# low_pass.net
KiCad netlist of a schematic drawn in Altium Designer
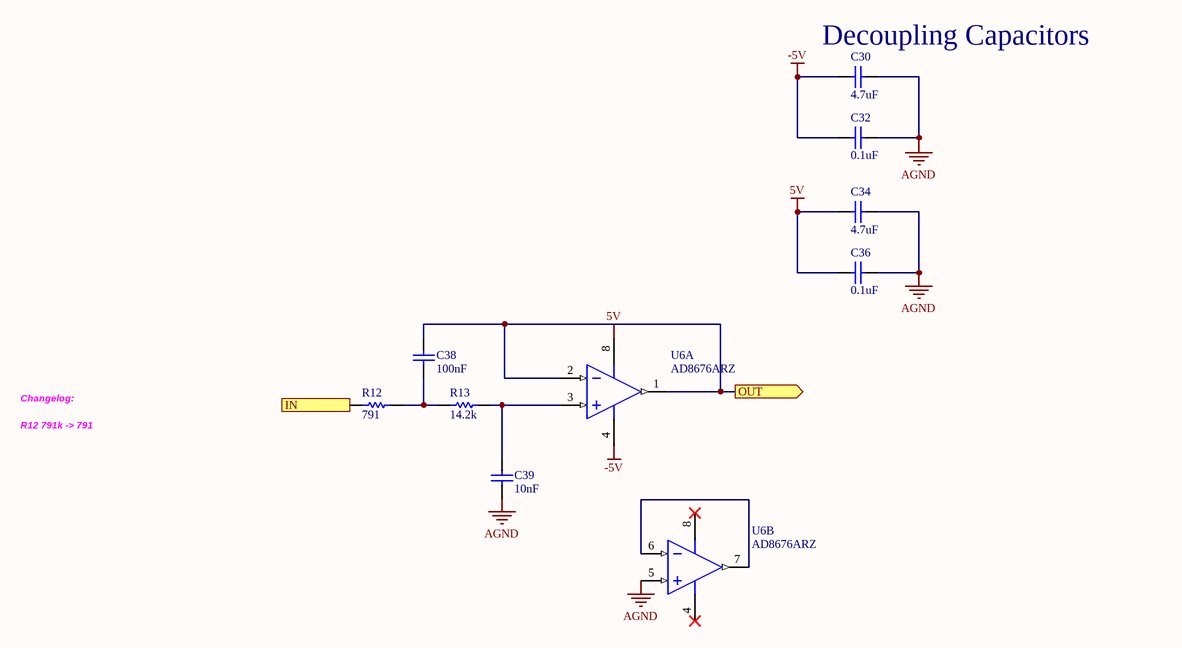
[diagram p0: low_pass.SchDoc]

(export (version "E")
  (design (tool "Eeschema 10.0.6"))
  (components
    (comp (ref "C30")
      (value "4.7uF")
      (footprint "0402_Cap")
      (description "Capacitor, 4.7uF, 0805")
      (libsource (lib "Arturo_Approved") (part "CL21A475KAQNNNE"))
    )
    (comp (ref "C32")
      (value "0.1uF")
      (footprint "0402_Cap")
      (description "Capacitor, 0.1uF, 0805")
      (libsource (lib "Arturo_Approved") (part "CL21B104KACNNNC"))
    )
    (comp (ref "C34")
      (value "4.7uF")
      (footprint "0402_Cap")
      (description "Capacitor, 4.7uF, 0805")
      (libsource (lib "Arturo_Approved") (part "CL21A475KAQNNNE"))
    )
    (comp (ref "C36")
      (value "0.1uF")
      (footprint "0402_Cap")
      (description "Capacitor, 0.1uF, 0805")
      (libsource (lib "Arturo_Approved") (part "CL21B104KACNNNC"))
    )
    (comp (ref "C38")
      (value "100nF")
      (footprint "0402_Cap")
      (description "Capacitor, 16nF, 0805, 25V")
      (libsource (lib "Arturo_Approved") (part "08051C163JAT2A"))
    )
    (comp (ref "C39")
      (value "10nF")
      (footprint "0402_Cap")
      (description "Capacitor, 1.6nF, 0805, 25V")
      (libsource (lib "Arturo_Approved") (part "GRM2165C2A162JA01D"))
    )
    (comp (ref "R12")
      (value "791")
      (footprint "0402_Res")
      (description "1.65k")
      (libsource (lib "Arturo_Approved") (part "RC0805FR-071K65L"))
    )
    (comp (ref "R13")
      (value "14.2k")
      (footprint "0402_Res")
      (description "5.9k")
      (libsource (lib "Arturo_Approved") (part "RC0805FR-075K9L"))
    )
    (comp (ref "U6")
      (value "AD8676ARZ")
      (footprint "ADI-R-8_M")
      (fields (field (name "GENERIC PART NUMBER") "AD8676") (field (name "MANUFACTURER") "Analog Devices"))
      (libsource (lib "Altium Content Vault") (part "ADI-OP29X-R-8"))
    )
  )
  (nets
    (net (code "1") (name "-5V") (class "Default")
      (node (ref "C30") (pin "1") (pinfunction "1_1") (pintype "passive"))
      (node (ref "C32") (pin "1") (pinfunction "1_1") (pintype "passive"))
      (node (ref "U6") (pin "4") (pinfunction "-V_4") (pintype "power_in"))
    )
    (net (code "2") (name "/IN") (class "Default")
      (node (ref "R12") (pin "1") (pinfunction "1_1") (pintype "passive"))
    )
    (net (code "3") (name "/OUT") (class "Default")
      (node (ref "C38") (pin "2") (pinfunction "2_2") (pintype "passive"))
      (node (ref "U6") (pin "1") (pinfunction "OUT_A_1") (pintype "output"))
      (node (ref "U6") (pin "2") (pinfunction "-IN_A_2") (pintype "input"))
    )
    (net (code "4") (name "5V") (class "Default")
      (node (ref "C34") (pin "1") (pinfunction "1_1") (pintype "passive"))
      (node (ref "C36") (pin "1") (pinfunction "1_1") (pintype "passive"))
      (node (ref "U6") (pin "8") (pinfunction "+V_8") (pintype "power_in"))
    )
    (net (code "5") (name "AGND") (class "Default")
      (node (ref "C30") (pin "2") (pinfunction "2_2") (pintype "passive"))
      (node (ref "C32") (pin "2") (pinfunction "2_2") (pintype "passive"))
      (node (ref "C34") (pin "2") (pinfunction "2_2") (pintype "passive"))
      (node (ref "C36") (pin "2") (pinfunction "2_2") (pintype "passive"))
      (node (ref "C39") (pin "1") (pinfunction "1_1") (pintype "passive"))
      (node (ref "U6") (pin "5") (pinfunction "+IN_B_5") (pintype "input"))
    )
    (net (code "6") (name "Net-(C38-Pad1)") (class "Default")
      (node (ref "C38") (pin "1") (pinfunction "1_1") (pintype "passive"))
      (node (ref "R12") (pin "2") (pinfunction "2_2") (pintype "passive"))
      (node (ref "R13") (pin "1") (pinfunction "1_1") (pintype "passive"))
    )
    (net (code "7") (name "Net-(U6A-+IN_A)") (class "Default")
      (node (ref "C39") (pin "2") (pinfunction "2_2") (pintype "passive"))
      (node (ref "R13") (pin "2") (pinfunction "2_2") (pintype "passive"))
      (node (ref "U6") (pin "3") (pinfunction "+IN_A_3") (pintype "input"))
    )
    (net (code "8") (name "Net-(U6B--IN_B)") (class "Default")
      (node (ref "U6") (pin "6") (pinfunction "-IN_B_6") (pintype "input"))
      (node (ref "U6") (pin "7") (pinfunction "OUT_B_7") (pintype "output"))
    )
    (net (code "9") (name "unconnected-(U6B-+V-Pad8)") (class "Default")
      (node (ref "U6") (pin "8") (pinfunction "+V_8") (pintype "power_in+no_connect"))
    )
    (net (code "10") (name "unconnected-(U6B--V-Pad4)") (class "Default")
      (node (ref "U6") (pin "4") (pinfunction "-V_4") (pintype "power_in+no_connect"))
    )
  )
)
